# Port_Deployable_Headers.net
KiCad netlist of a schematic drawn in Altium Designer
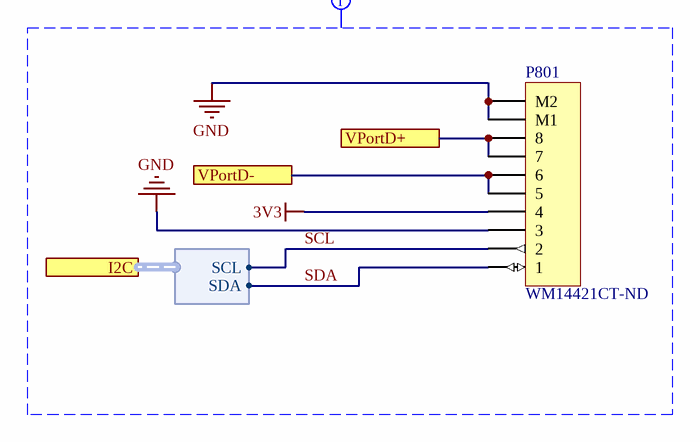
[diagram p0: Port_Deployable_Headers.SchDoc]

(export (version "E")
  (design (tool "Eeschema 10.0.6"))
  (components
    (comp (ref "P801")
      (value "WM14421CT-ND")
      (footprint "MOLX-5040500891")
      (description "CONN HEADER SMD R/A 8POS 1.5MM")
      (fields
        (field (name "PART NUMBER") "67")
        (field (name "MANUFACTURER PART NUMBER") "5040500891")
        (field (name "PUBLISHER") "Altium Limited")
      )
      (libsource (lib "Database") (part "Header 10"))
    )
  )
  (nets
    (net (code "2") (name "/SCL") (class "Default")
      (node (ref "P801") (pin "2") (pinfunction "2_2") (pintype "output"))
    )
    (net (code "3") (name "/SDA") (class "Default")
      (node (ref "P801") (pin "1") (pinfunction "1_1") (pintype "bidirectional"))
    )
    (net (code "4") (name "/VPortD+") (class "Default")
      (node (ref "P801") (pin "7") (pinfunction "7_7") (pintype "passive"))
      (node (ref "P801") (pin "8") (pinfunction "8_8") (pintype "passive"))
    )
    (net (code "5") (name "/VPortD-") (class "Default")
      (node (ref "P801") (pin "5") (pinfunction "5_5") (pintype "passive"))
      (node (ref "P801") (pin "6") (pinfunction "6_6") (pintype "passive"))
    )
    (net (code "7") (name "3V3") (class "Default")
      (node (ref "P801") (pin "4") (pinfunction "4_4") (pintype "passive"))
    )
    (net (code "8") (name "GND") (class "Default")
      (node (ref "P801") (pin "3") (pinfunction "3_3") (pintype "passive"))
      (node (ref "P801") (pin "M1") (pinfunction "M1_M1") (pintype "passive"))
      (node (ref "P801") (pin "M2") (pinfunction "M2_M2") (pintype "passive"))
    )
  )
)
